# 8x8matrix_tlc3.net
KiCad netlist of a schematic drawn in EAGLE
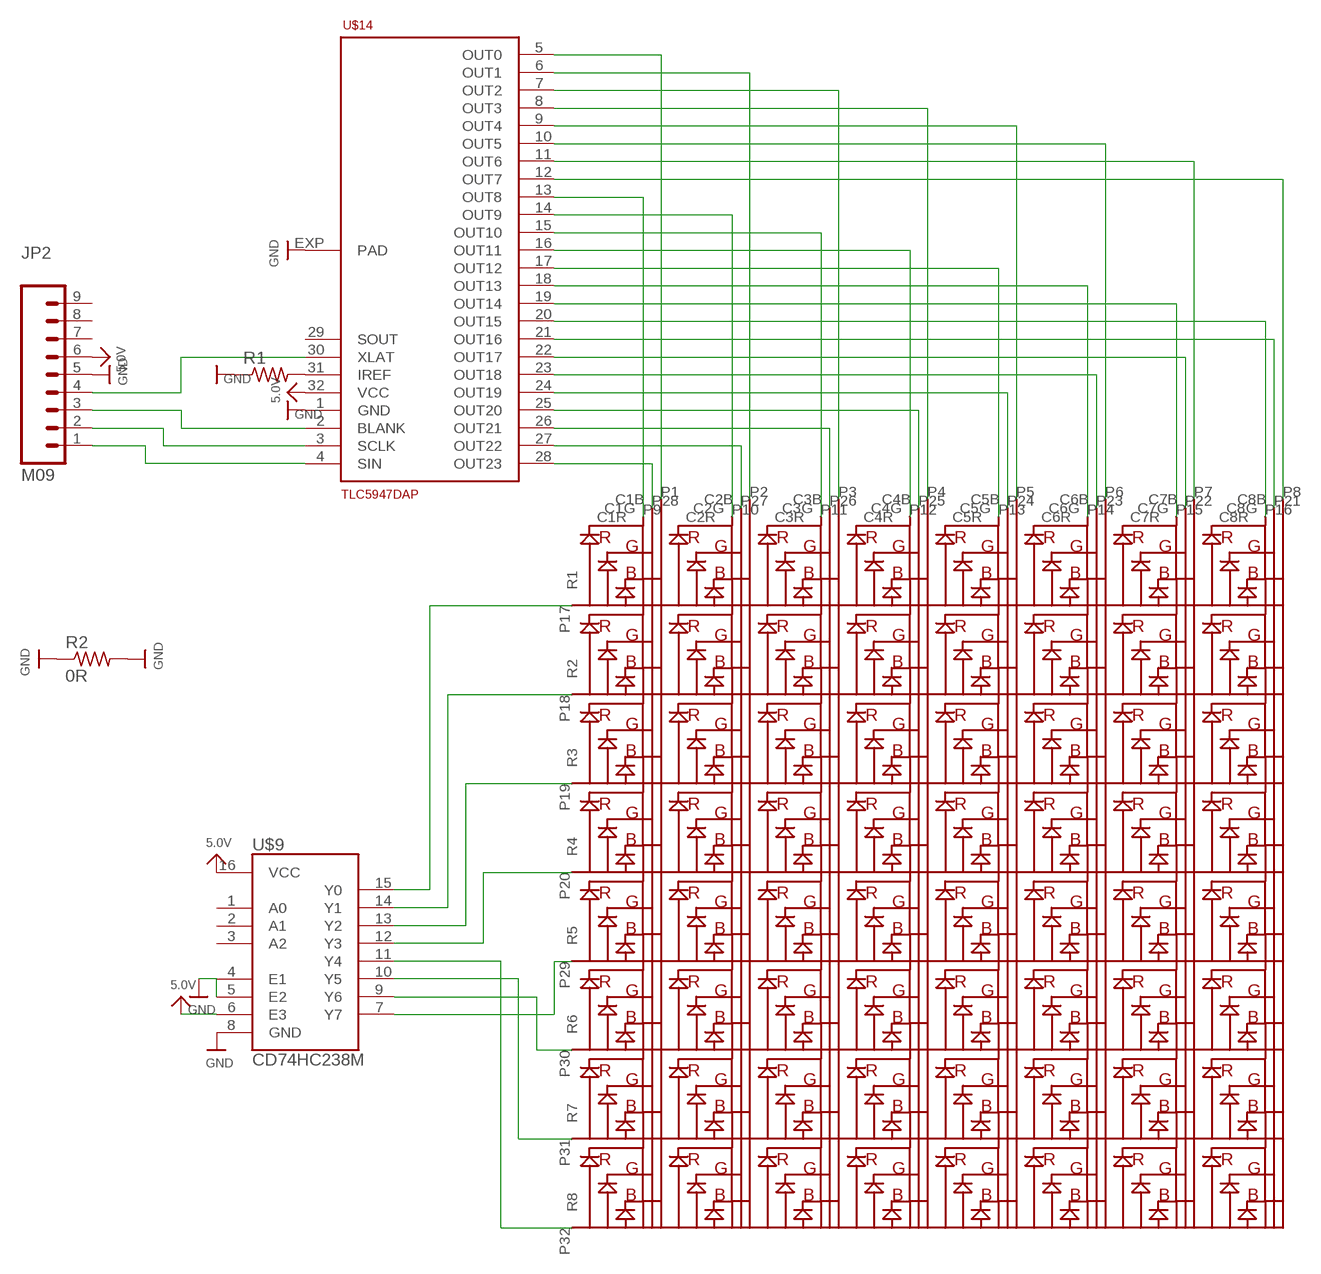
[diagram p0: schematic, sheet 1]

(export (version "E")
  (design (tool "Eeschema 10.0.6"))
  (components
    (comp (ref "JP2")
      (value "M09")
      (footprint "eagle-import:1X09")
      (libsource (lib "eagle-import") (part "M09"))
    )
    (comp (ref "R1")
      (value "R-US_R0805")
      (footprint "eagle-import:R0805")
      (libsource (lib "eagle-import") (part "R-US_R0805"))
    )
    (comp (ref "R2")
      (value "0R")
      (footprint "eagle-import:M1206")
      (libsource (lib "eagle-import") (part "R-US_M1206"))
    )
    (comp (ref "U$1")
      (value "GTM2088ARGB")
      (footprint "eagle-import:8X8MATRIX")
      (libsource (lib "eagle-import") (part "GTM2088ARGB"))
    )
    (comp (ref "U$9")
      (value "CD74HC238M")
      (footprint "eagle-import:SO-16")
      (libsource (lib "eagle-import") (part "CD74HC238M"))
    )
    (comp (ref "U$14")
      (value "TLC5947DAP")
      (footprint "eagle-import:HTSSOP32DAP")
      (libsource (lib "eagle-import") (part "TLC5947DAP"))
    )
  )
  (nets
    (net (code "1") (name "5.0V") (class "Default")
      (node (ref "JP2") (pin "6") (pinfunction "6_6") (pintype "passive"))
      (node (ref "U$14") (pin "32") (pinfunction "VCC_32") (pintype "bidirectional"))
      (node (ref "U$9") (pin "16") (pinfunction "VCC_16") (pintype "bidirectional"))
      (node (ref "U$9") (pin "6") (pinfunction "E3_6") (pintype "bidirectional"))
    )
    (net (code "2") (name "GND") (class "Default")
      (node (ref "JP2") (pin "5") (pinfunction "5_5") (pintype "passive"))
      (node (ref "R1") (pin "1") (pinfunction "1_1") (pintype "passive"))
      (node (ref "R2") (pin "1") (pinfunction "1_1") (pintype "passive"))
      (node (ref "R2") (pin "2") (pinfunction "2_2") (pintype "passive"))
      (node (ref "U$14") (pin "1") (pinfunction "GND_1") (pintype "bidirectional"))
      (node (ref "U$14") (pin "EXP") (pinfunction "PAD_EXP") (pintype "bidirectional"))
      (node (ref "U$9") (pin "4") (pinfunction "E1_4") (pintype "bidirectional"))
      (node (ref "U$9") (pin "5") (pinfunction "E2_5") (pintype "bidirectional"))
      (node (ref "U$9") (pin "8") (pinfunction "GND_8") (pintype "bidirectional"))
    )
    (net (code "3") (name "Net-(U$1-C1B)") (class "Default")
      (node (ref "U$1") (pin "P1") (pinfunction "C1B_P1") (pintype "bidirectional"))
      (node (ref "U$14") (pin "5") (pinfunction "OUT0_5") (pintype "bidirectional"))
    )
    (net (code "4") (name "Net-(U$1-C1G)") (class "Default")
      (node (ref "U$1") (pin "P28") (pinfunction "C1G_P28") (pintype "bidirectional"))
      (node (ref "U$14") (pin "28") (pinfunction "OUT23_28") (pintype "bidirectional"))
    )
    (net (code "5") (name "Net-(U$1-C1R)") (class "Default")
      (node (ref "U$1") (pin "P9") (pinfunction "C1R_P9") (pintype "bidirectional"))
      (node (ref "U$14") (pin "13") (pinfunction "OUT8_13") (pintype "bidirectional"))
    )
    (net (code "6") (name "Net-(U$1-C2B)") (class "Default")
      (node (ref "U$1") (pin "P2") (pinfunction "C2B_P2") (pintype "bidirectional"))
      (node (ref "U$14") (pin "6") (pinfunction "OUT1_6") (pintype "bidirectional"))
    )
    (net (code "7") (name "Net-(U$1-C2G)") (class "Default")
      (node (ref "U$1") (pin "P27") (pinfunction "C2G_P27") (pintype "bidirectional"))
      (node (ref "U$14") (pin "27") (pinfunction "OUT22_27") (pintype "bidirectional"))
    )
    (net (code "8") (name "Net-(U$1-C2R)") (class "Default")
      (node (ref "U$1") (pin "P10") (pinfunction "C2R_P10") (pintype "bidirectional"))
      (node (ref "U$14") (pin "14") (pinfunction "OUT9_14") (pintype "bidirectional"))
    )
    (net (code "9") (name "Net-(U$1-C3B)") (class "Default")
      (node (ref "U$1") (pin "P3") (pinfunction "C3B_P3") (pintype "bidirectional"))
      (node (ref "U$14") (pin "7") (pinfunction "OUT2_7") (pintype "bidirectional"))
    )
    (net (code "10") (name "Net-(U$1-C3G)") (class "Default")
      (node (ref "U$1") (pin "P26") (pinfunction "C3G_P26") (pintype "bidirectional"))
      (node (ref "U$14") (pin "26") (pinfunction "OUT21_26") (pintype "bidirectional"))
    )
    (net (code "11") (name "Net-(U$1-C3R)") (class "Default")
      (node (ref "U$1") (pin "P11") (pinfunction "C3R_P11") (pintype "bidirectional"))
      (node (ref "U$14") (pin "15") (pinfunction "OUT10_15") (pintype "bidirectional"))
    )
    (net (code "12") (name "Net-(U$1-C4B)") (class "Default")
      (node (ref "U$1") (pin "P4") (pinfunction "C4B_P4") (pintype "bidirectional"))
      (node (ref "U$14") (pin "8") (pinfunction "OUT3_8") (pintype "bidirectional"))
    )
    (net (code "13") (name "Net-(U$1-C4G)") (class "Default")
      (node (ref "U$1") (pin "P25") (pinfunction "C4G_P25") (pintype "bidirectional"))
      (node (ref "U$14") (pin "25") (pinfunction "OUT20_25") (pintype "bidirectional"))
    )
    (net (code "14") (name "Net-(U$1-C4R)") (class "Default")
      (node (ref "U$1") (pin "P12") (pinfunction "C4R_P12") (pintype "bidirectional"))
      (node (ref "U$14") (pin "16") (pinfunction "OUT11_16") (pintype "bidirectional"))
    )
    (net (code "15") (name "Net-(U$1-C5B)") (class "Default")
      (node (ref "U$1") (pin "P5") (pinfunction "C5B_P5") (pintype "bidirectional"))
      (node (ref "U$14") (pin "9") (pinfunction "OUT4_9") (pintype "bidirectional"))
    )
    (net (code "16") (name "Net-(U$1-C5G)") (class "Default")
      (node (ref "U$1") (pin "P24") (pinfunction "C5G_P24") (pintype "bidirectional"))
      (node (ref "U$14") (pin "24") (pinfunction "OUT19_24") (pintype "bidirectional"))
    )
    (net (code "17") (name "Net-(U$1-C5R)") (class "Default")
      (node (ref "U$1") (pin "P13") (pinfunction "C5R_P13") (pintype "bidirectional"))
      (node (ref "U$14") (pin "17") (pinfunction "OUT12_17") (pintype "bidirectional"))
    )
    (net (code "18") (name "Net-(U$1-C6B)") (class "Default")
      (node (ref "U$1") (pin "P6") (pinfunction "C6B_P6") (pintype "bidirectional"))
      (node (ref "U$14") (pin "10") (pinfunction "OUT5_10") (pintype "bidirectional"))
    )
    (net (code "19") (name "Net-(U$1-C6G)") (class "Default")
      (node (ref "U$1") (pin "P23") (pinfunction "C6G_P23") (pintype "bidirectional"))
      (node (ref "U$14") (pin "23") (pinfunction "OUT18_23") (pintype "bidirectional"))
    )
    (net (code "20") (name "Net-(U$1-C6R)") (class "Default")
      (node (ref "U$1") (pin "P14") (pinfunction "C6R_P14") (pintype "bidirectional"))
      (node (ref "U$14") (pin "18") (pinfunction "OUT13_18") (pintype "bidirectional"))
    )
    (net (code "21") (name "Net-(U$1-C7B)") (class "Default")
      (node (ref "U$1") (pin "P7") (pinfunction "C7B_P7") (pintype "bidirectional"))
      (node (ref "U$14") (pin "11") (pinfunction "OUT6_11") (pintype "bidirectional"))
    )
    (net (code "22") (name "Net-(U$1-C7G)") (class "Default")
      (node (ref "U$1") (pin "P22") (pinfunction "C7G_P22") (pintype "bidirectional"))
      (node (ref "U$14") (pin "22") (pinfunction "OUT17_22") (pintype "bidirectional"))
    )
    (net (code "23") (name "Net-(U$1-C7R)") (class "Default")
      (node (ref "U$1") (pin "P15") (pinfunction "C7R_P15") (pintype "bidirectional"))
      (node (ref "U$14") (pin "19") (pinfunction "OUT14_19") (pintype "bidirectional"))
    )
    (net (code "24") (name "Net-(U$1-C8B)") (class "Default")
      (node (ref "U$1") (pin "P8") (pinfunction "C8B_P8") (pintype "bidirectional"))
      (node (ref "U$14") (pin "12") (pinfunction "OUT7_12") (pintype "bidirectional"))
    )
    (net (code "25") (name "Net-(U$1-C8G)") (class "Default")
      (node (ref "U$1") (pin "P21") (pinfunction "C8G_P21") (pintype "bidirectional"))
      (node (ref "U$14") (pin "21") (pinfunction "OUT16_21") (pintype "bidirectional"))
    )
    (net (code "26") (name "Net-(U$1-C8R)") (class "Default")
      (node (ref "U$1") (pin "P16") (pinfunction "C8R_P16") (pintype "bidirectional"))
      (node (ref "U$14") (pin "20") (pinfunction "OUT15_20") (pintype "bidirectional"))
    )
    (net (code "27") (name "Net-(U$1-R1)") (class "Default")
      (node (ref "U$1") (pin "P17") (pinfunction "R1_P17") (pintype "bidirectional"))
      (node (ref "U$9") (pin "15") (pinfunction "Y0_15") (pintype "bidirectional"))
    )
    (net (code "28") (name "Net-(U$1-R2)") (class "Default")
      (node (ref "U$1") (pin "P18") (pinfunction "R2_P18") (pintype "bidirectional"))
      (node (ref "U$9") (pin "14") (pinfunction "Y1_14") (pintype "bidirectional"))
    )
    (net (code "29") (name "Net-(U$1-R3)") (class "Default")
      (node (ref "U$1") (pin "P19") (pinfunction "R3_P19") (pintype "bidirectional"))
      (node (ref "U$9") (pin "13") (pinfunction "Y2_13") (pintype "bidirectional"))
    )
    (net (code "30") (name "Net-(U$1-R4)") (class "Default")
      (node (ref "U$1") (pin "P20") (pinfunction "R4_P20") (pintype "bidirectional"))
      (node (ref "U$9") (pin "12") (pinfunction "Y3_12") (pintype "bidirectional"))
    )
    (net (code "31") (name "Net-(U$1-R5)") (class "Default")
      (node (ref "U$1") (pin "P29") (pinfunction "R5_P29") (pintype "bidirectional"))
      (node (ref "U$9") (pin "7") (pinfunction "Y7_7") (pintype "bidirectional"))
    )
    (net (code "32") (name "Net-(U$1-R6)") (class "Default")
      (node (ref "U$1") (pin "P30") (pinfunction "R6_P30") (pintype "bidirectional"))
      (node (ref "U$9") (pin "9") (pinfunction "Y6_9") (pintype "bidirectional"))
    )
    (net (code "33") (name "Net-(U$1-R7)") (class "Default")
      (node (ref "U$1") (pin "P31") (pinfunction "R7_P31") (pintype "bidirectional"))
      (node (ref "U$9") (pin "10") (pinfunction "Y5_10") (pintype "bidirectional"))
    )
    (net (code "34") (name "Net-(U$1-R8)") (class "Default")
      (node (ref "U$1") (pin "P32") (pinfunction "R8_P32") (pintype "bidirectional"))
      (node (ref "U$9") (pin "11") (pinfunction "Y4_11") (pintype "bidirectional"))
    )
    (net (code "35") (name "Net-(U$14-BLANK)") (class "Default")
      (node (ref "JP2") (pin "3") (pinfunction "3_3") (pintype "passive"))
      (node (ref "U$14") (pin "2") (pinfunction "BLANK_2") (pintype "bidirectional"))
    )
    (net (code "36") (name "Net-(U$14-IREF)") (class "Default")
      (node (ref "R1") (pin "2") (pinfunction "2_2") (pintype "passive"))
      (node (ref "U$14") (pin "31") (pinfunction "IREF_31") (pintype "bidirectional"))
    )
    (net (code "37") (name "Net-(U$14-SCLK)") (class "Default")
      (node (ref "JP2") (pin "2") (pinfunction "2_2") (pintype "passive"))
      (node (ref "U$14") (pin "3") (pinfunction "SCLK_3") (pintype "bidirectional"))
    )
    (net (code "38") (name "Net-(U$14-SIN)") (class "Default")
      (node (ref "JP2") (pin "1") (pinfunction "1_1") (pintype "passive"))
      (node (ref "U$14") (pin "4") (pinfunction "SIN_4") (pintype "bidirectional"))
    )
    (net (code "39") (name "Net-(U$14-XLAT)") (class "Default")
      (node (ref "JP2") (pin "4") (pinfunction "4_4") (pintype "passive"))
      (node (ref "U$14") (pin "30") (pinfunction "XLAT_30") (pintype "bidirectional"))
    )
    (net (code "40") (name "unconnected-(JP2-Pad7)") (class "Default")
      (node (ref "JP2") (pin "7") (pinfunction "7_7") (pintype "passive"))
    )
    (net (code "41") (name "unconnected-(JP2-Pad8)") (class "Default")
      (node (ref "JP2") (pin "8") (pinfunction "8_8") (pintype "passive"))
    )
    (net (code "42") (name "unconnected-(JP2-Pad9)") (class "Default")
      (node (ref "JP2") (pin "9") (pinfunction "9_9") (pintype "passive"))
    )
    (net (code "43") (name "unconnected-(U$9-A0-Pad1)") (class "Default")
      (node (ref "U$9") (pin "1") (pinfunction "A0_1") (pintype "bidirectional"))
    )
    (net (code "44") (name "unconnected-(U$9-A1-Pad2)") (class "Default")
      (node (ref "U$9") (pin "2") (pinfunction "A1_2") (pintype "bidirectional"))
    )
    (net (code "45") (name "unconnected-(U$9-A2-Pad3)") (class "Default")
      (node (ref "U$9") (pin "3") (pinfunction "A2_3") (pintype "bidirectional"))
    )
    (net (code "46") (name "unconnected-(U$14-SOUT-Pad29)") (class "Default")
      (node (ref "U$14") (pin "29") (pinfunction "SOUT_29") (pintype "bidirectional"))
    )
  )
)
